# Lab_1_3.net
KiCad netlist of a schematic drawn in EAGLE
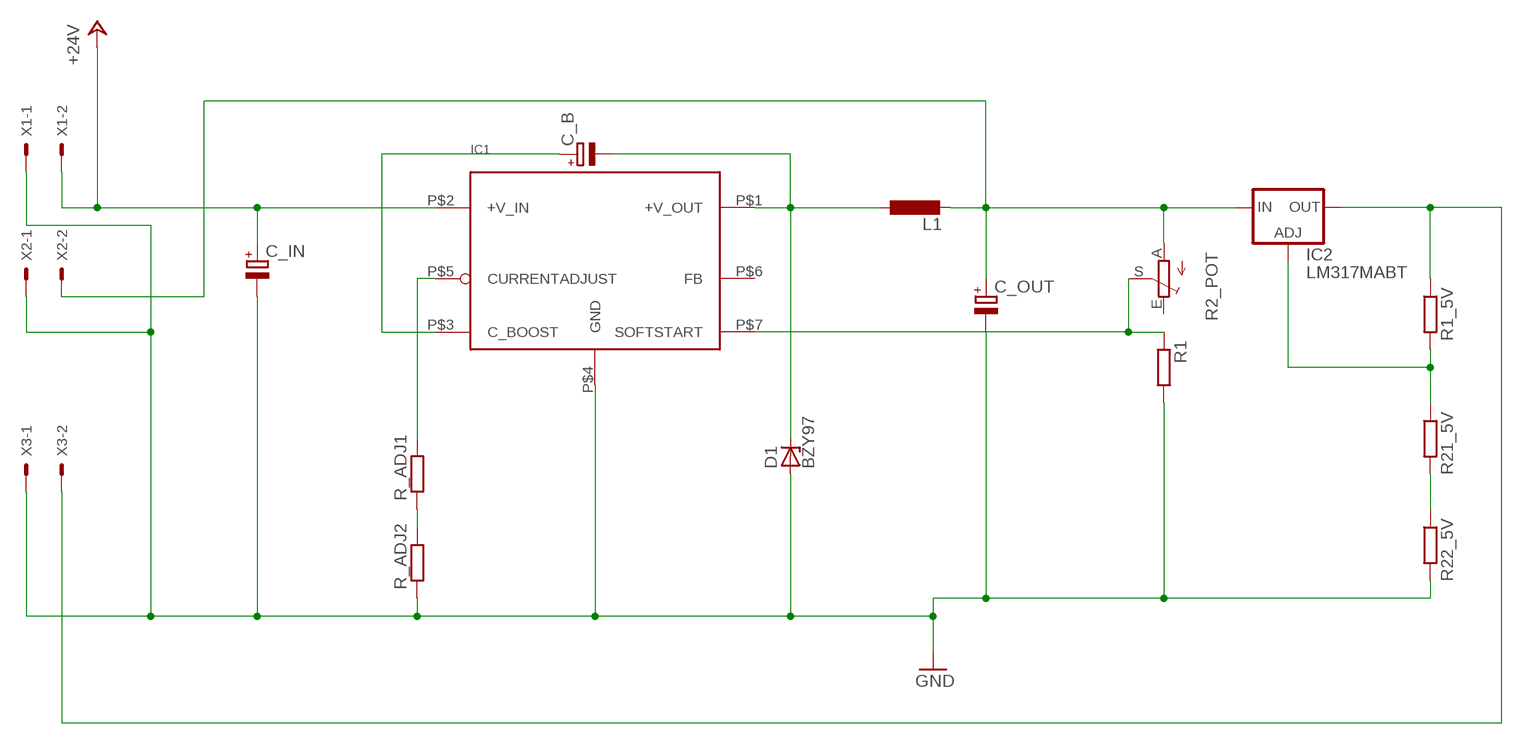
[diagram p0: schematic, sheet 1]

(export (version "E")
  (design (tool "Eeschema 10.0.6"))
  (components
    (comp (ref "C_B")
      (value "CPOL-EUETR2")
      (footprint "eagle-import:ETR2")
      (libsource (lib "eagle-import") (part "CPOL-EUETR2"))
    )
    (comp (ref "C_IN")
      (value "CPOL-EUE5-13")
      (footprint "eagle-import:E5-13")
      (libsource (lib "eagle-import") (part "CPOL-EUE5-13"))
    )
    (comp (ref "C_OUT")
      (value "CPOL-EUE5-10.5")
      (footprint "eagle-import:E5-10,5")
      (libsource (lib "eagle-import") (part "CPOL-EUE5-10.5"))
    )
    (comp (ref "D1")
      (value "BZY97")
      (footprint "eagle-import:F126Z12")
      (libsource (lib "eagle-import") (part "BZY97"))
    )
    (comp (ref "IC1")
      (value "LM2576-T05D")
      (footprint "eagle-import:TO220-5_STAGGERED")
      (libsource (lib "eagle-import") (part "LM2576-T05D"))
    )
    (comp (ref "IC2")
      (value "LM317MABT")
      (footprint "eagle-import:TO220L1")
      (libsource (lib "eagle-import") (part "LM317?MABT"))
    )
    (comp (ref "L1")
      (value "L-EUTJ4-U2")
      (footprint "eagle-import:TJ4-U2")
      (libsource (lib "eagle-import") (part "L-EUTJ4-U2"))
    )
    (comp (ref "R1")
      (value "R-EU_0309/12")
      (footprint "eagle-import:0309_12")
      (libsource (lib "eagle-import") (part "R-EU_0309/12"))
    )
    (comp (ref "R1_5V")
      (value "R-EU_0309/12")
      (footprint "eagle-import:0309_12")
      (libsource (lib "eagle-import") (part "R-EU_0309/12"))
    )
    (comp (ref "R2_POT")
      (value "TRIM_EU-B25P")
      (footprint "eagle-import:B25P")
      (libsource (lib "eagle-import") (part "TRIM_EU-B25P"))
    )
    (comp (ref "R21_5V")
      (value "R-EU_0309/12")
      (footprint "eagle-import:0309_12")
      (libsource (lib "eagle-import") (part "R-EU_0309/12"))
    )
    (comp (ref "R22_5V")
      (value "R-EU_0309/12")
      (footprint "eagle-import:0309_12")
      (libsource (lib "eagle-import") (part "R-EU_0309/12"))
    )
    (comp (ref "R_ADJ1")
      (value "R-EU_0309/12")
      (footprint "eagle-import:0309_12")
      (libsource (lib "eagle-import") (part "R-EU_0309/12"))
    )
    (comp (ref "R_ADJ2")
      (value "R-EU_0309/12")
      (footprint "eagle-import:0309_12")
      (libsource (lib "eagle-import") (part "R-EU_0309/12"))
    )
    (comp (ref "X1")
      (value "KK-156-2")
      (footprint "eagle-import:KK-156-2")
      (libsource (lib "eagle-import") (part "KK-156-2"))
    )
    (comp (ref "X2")
      (value "KK-156-2")
      (footprint "eagle-import:KK-156-2")
      (libsource (lib "eagle-import") (part "KK-156-2"))
    )
    (comp (ref "X3")
      (value "KK-156-2")
      (footprint "eagle-import:KK-156-2")
      (libsource (lib "eagle-import") (part "KK-156-2"))
    )
  )
  (nets
    (net (code "1") (name "+24V") (class "Default")
      (node (ref "C_IN") (pin "+") (pinfunction "+_+") (pintype "passive"))
      (node (ref "IC1") (pin "P$2") (pinfunction "+V_IN_P$2") (pintype "input"))
      (node (ref "X1") (pin "2") (pinfunction "S_2") (pintype "passive"))
    )
    (net (code "2") (name "GND") (class "Default")
      (node (ref "C_IN") (pin "-") (pinfunction "-_-") (pintype "passive"))
      (node (ref "C_OUT") (pin "-") (pinfunction "-_-") (pintype "passive"))
      (node (ref "D1") (pin "A") (pinfunction "A_A") (pintype "passive"))
      (node (ref "IC1") (pin "P$4") (pinfunction "GND_P$4") (pintype "power_in"))
      (node (ref "R1") (pin "2") (pinfunction "2_2") (pintype "passive"))
      (node (ref "R22_5V") (pin "2") (pinfunction "2_2") (pintype "passive"))
      (node (ref "R_ADJ2") (pin "1") (pinfunction "1_1") (pintype "passive"))
      (node (ref "X1") (pin "1") (pinfunction "S_1") (pintype "passive"))
      (node (ref "X2") (pin "1") (pinfunction "S_1") (pintype "passive"))
      (node (ref "X3") (pin "1") (pinfunction "S_1") (pintype "passive"))
    )
    (net (code "3") (name "Net-(IC1-+V_OUT)") (class "Default")
      (node (ref "C_B") (pin "-") (pinfunction "-_-") (pintype "passive"))
      (node (ref "D1") (pin "C") (pinfunction "C_C") (pintype "passive"))
      (node (ref "IC1") (pin "P$1") (pinfunction "+V_OUT_P$1") (pintype "output"))
      (node (ref "L1") (pin "1") (pinfunction "1_1") (pintype "passive"))
    )
    (net (code "4") (name "Net-(IC1-CURRENTADJUST)") (class "Default")
      (node (ref "IC1") (pin "P$5") (pinfunction "CURRENTADJUST_P$5") (pintype "input"))
      (node (ref "R_ADJ1") (pin "2") (pinfunction "2_2") (pintype "passive"))
    )
    (net (code "5") (name "Net-(IC1-C_BOOST)") (class "Default")
      (node (ref "C_B") (pin "+") (pinfunction "+_+") (pintype "passive"))
      (node (ref "IC1") (pin "P$3") (pinfunction "C_BOOST_P$3") (pintype "input"))
    )
    (net (code "6") (name "Net-(IC1-SOFTSTART)") (class "Default")
      (node (ref "IC1") (pin "P$7") (pinfunction "SOFTSTART_P$7") (pintype "input"))
      (node (ref "R1") (pin "1") (pinfunction "1_1") (pintype "passive"))
      (node (ref "R2_POT") (pin "S") (pinfunction "S_S") (pintype "passive"))
    )
    (net (code "7") (name "Net-(IC2-ADJ)") (class "Default")
      (node (ref "IC2") (pin "1") (pinfunction "ADJ_1") (pintype "input"))
      (node (ref "R1_5V") (pin "2") (pinfunction "2_2") (pintype "passive"))
      (node (ref "R21_5V") (pin "1") (pinfunction "1_1") (pintype "passive"))
    )
    (net (code "8") (name "Net-(IC2-IN)") (class "Default")
      (node (ref "C_OUT") (pin "+") (pinfunction "+_+") (pintype "passive"))
      (node (ref "IC2") (pin "3") (pinfunction "IN_3") (pintype "input"))
      (node (ref "L1") (pin "2") (pinfunction "2_2") (pintype "passive"))
      (node (ref "R2_POT") (pin "A") (pinfunction "A_A") (pintype "passive"))
      (node (ref "X2") (pin "2") (pinfunction "S_2") (pintype "passive"))
    )
    (net (code "9") (name "Net-(IC2-OUT)") (class "Default")
      (node (ref "IC2") (pin "2") (pinfunction "OUT_2") (pintype "passive"))
      (node (ref "R1_5V") (pin "1") (pinfunction "1_1") (pintype "passive"))
      (node (ref "X3") (pin "2") (pinfunction "S_2") (pintype "passive"))
    )
    (net (code "10") (name "Net-(R21_5V-Pad2)") (class "Default")
      (node (ref "R21_5V") (pin "2") (pinfunction "2_2") (pintype "passive"))
      (node (ref "R22_5V") (pin "1") (pinfunction "1_1") (pintype "passive"))
    )
    (net (code "11") (name "Net-(R_ADJ1-Pad1)") (class "Default")
      (node (ref "R_ADJ1") (pin "1") (pinfunction "1_1") (pintype "passive"))
      (node (ref "R_ADJ2") (pin "2") (pinfunction "2_2") (pintype "passive"))
    )
    (net (code "12") (name "unconnected-(IC1-FB-PadP$6)") (class "Default")
      (node (ref "IC1") (pin "P$6") (pinfunction "FB_P$6") (pintype "input"))
    )
    (net (code "13") (name "unconnected-(R2_POT-PadE)") (class "Default")
      (node (ref "R2_POT") (pin "E") (pinfunction "E_E") (pintype "passive"))
    )
  )
)
